# armBandHeaderShield.net
KiCad netlist of a schematic drawn in EAGLE
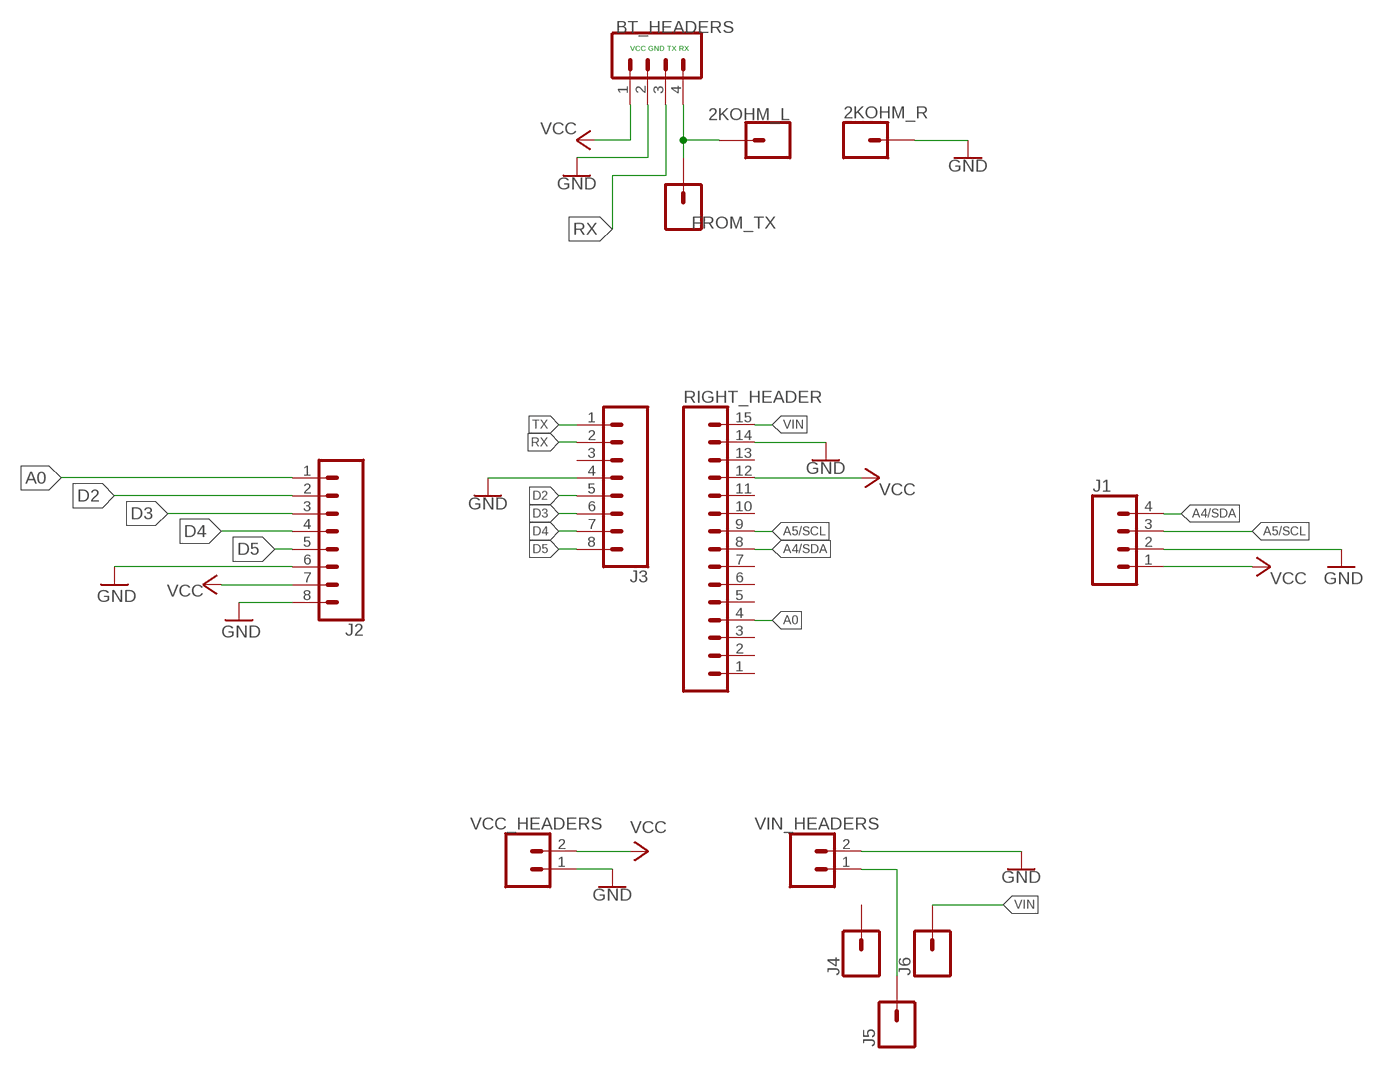
[diagram p0: schematic, sheet 1]

(export (version "E")
  (design (tool "Eeschema 10.0.6"))
  (components
    (comp (ref "2KOHM_L")
      (value "CONN_01")
      (footprint "eagle-import:1X01")
      (libsource (lib "eagle-import") (part "CONN_01"))
    )
    (comp (ref "2KOHM_R")
      (value "CONN_01")
      (footprint "eagle-import:1X01")
      (libsource (lib "eagle-import") (part "CONN_01"))
    )
    (comp (ref "BT_HEADERS")
      (value "CONN_04")
      (footprint "eagle-import:1X04")
      (libsource (lib "eagle-import") (part "CONN_04"))
    )
    (comp (ref "FROM_TX")
      (value "CONN_01")
      (footprint "eagle-import:1X01")
      (libsource (lib "eagle-import") (part "CONN_01"))
    )
    (comp (ref "J1")
      (value "CONN_04")
      (footprint "eagle-import:1X04")
      (libsource (lib "eagle-import") (part "CONN_04"))
    )
    (comp (ref "J2")
      (value "CONN_08\"")
      (footprint "eagle-import:1X08")
      (libsource (lib "eagle-import") (part "CONN_08{dblquote}"))
    )
    (comp (ref "J3")
      (value "CONN_08\"")
      (footprint "eagle-import:1X08")
      (libsource (lib "eagle-import") (part "CONN_08{dblquote}"))
    )
    (comp (ref "J4")
      (value "CONN_01")
      (footprint "eagle-import:1X01")
      (libsource (lib "eagle-import") (part "CONN_01"))
    )
    (comp (ref "J5")
      (value "CONN_01")
      (footprint "eagle-import:1X01")
      (libsource (lib "eagle-import") (part "CONN_01"))
    )
    (comp (ref "J6")
      (value "CONN_01")
      (footprint "eagle-import:1X01")
      (libsource (lib "eagle-import") (part "CONN_01"))
    )
    (comp (ref "RIGHT_HEADER")
      (value "CONN_15")
      (footprint "eagle-import:1X15")
      (libsource (lib "eagle-import") (part "CONN_15"))
    )
    (comp (ref "VCC_HEADERS")
      (value "CONN_02")
      (footprint "eagle-import:1X02")
      (libsource (lib "eagle-import") (part "CONN_02"))
    )
    (comp (ref "VIN_HEADERS")
      (value "CONN_02PTH3")
      (footprint "eagle-import:1X02_LONGPADS")
      (libsource (lib "eagle-import") (part "CONN_02PTH3"))
    )
  )
  (nets
    (net (code "1") (name "A0") (class "Default")
      (node (ref "J2") (pin "1") (pinfunction "1_1") (pintype "passive"))
      (node (ref "RIGHT_HEADER") (pin "4") (pinfunction "4_4") (pintype "passive"))
    )
    (net (code "2") (name "A4{slash}SDA") (class "Default")
      (node (ref "J1") (pin "4") (pinfunction "4_4") (pintype "passive"))
      (node (ref "RIGHT_HEADER") (pin "8") (pinfunction "8_8") (pintype "passive"))
    )
    (net (code "3") (name "A5{slash}SCL") (class "Default")
      (node (ref "J1") (pin "3") (pinfunction "3_3") (pintype "passive"))
      (node (ref "RIGHT_HEADER") (pin "9") (pinfunction "9_9") (pintype "passive"))
    )
    (net (code "4") (name "D2") (class "Default")
      (node (ref "J2") (pin "2") (pinfunction "2_2") (pintype "passive"))
      (node (ref "J3") (pin "5") (pinfunction "5_5") (pintype "passive"))
    )
    (net (code "5") (name "D3") (class "Default")
      (node (ref "J2") (pin "3") (pinfunction "3_3") (pintype "passive"))
      (node (ref "J3") (pin "6") (pinfunction "6_6") (pintype "passive"))
    )
    (net (code "6") (name "D4") (class "Default")
      (node (ref "J2") (pin "4") (pinfunction "4_4") (pintype "passive"))
      (node (ref "J3") (pin "7") (pinfunction "7_7") (pintype "passive"))
    )
    (net (code "7") (name "D5") (class "Default")
      (node (ref "J2") (pin "5") (pinfunction "5_5") (pintype "passive"))
      (node (ref "J3") (pin "8") (pinfunction "8_8") (pintype "passive"))
    )
    (net (code "8") (name "GND") (class "Default")
      (node (ref "2KOHM_R") (pin "1") (pinfunction "1_1") (pintype "passive"))
      (node (ref "BT_HEADERS") (pin "2") (pinfunction "2_2") (pintype "passive"))
      (node (ref "J1") (pin "2") (pinfunction "2_2") (pintype "passive"))
      (node (ref "J2") (pin "6") (pinfunction "6_6") (pintype "passive"))
      (node (ref "J2") (pin "8") (pinfunction "8_8") (pintype "passive"))
      (node (ref "J3") (pin "4") (pinfunction "4_4") (pintype "passive"))
      (node (ref "RIGHT_HEADER") (pin "14") (pinfunction "14_14") (pintype "passive"))
      (node (ref "VCC_HEADERS") (pin "1") (pinfunction "1_1") (pintype "passive"))
      (node (ref "VIN_HEADERS") (pin "2") (pinfunction "2_2") (pintype "passive"))
    )
    (net (code "9") (name "Net-(2KOHM_L-Pad1)") (class "Default")
      (node (ref "2KOHM_L") (pin "1") (pinfunction "1_1") (pintype "passive"))
      (node (ref "BT_HEADERS") (pin "4") (pinfunction "4_4") (pintype "passive"))
      (node (ref "FROM_TX") (pin "1") (pinfunction "1_1") (pintype "passive"))
    )
    (net (code "10") (name "Net-(J5-Pad1)") (class "Default")
      (node (ref "J5") (pin "1") (pinfunction "1_1") (pintype "passive"))
      (node (ref "VIN_HEADERS") (pin "1") (pinfunction "1_1") (pintype "passive"))
    )
    (net (code "11") (name "RX") (class "Default")
      (node (ref "BT_HEADERS") (pin "3") (pinfunction "3_3") (pintype "passive"))
      (node (ref "J3") (pin "2") (pinfunction "2_2") (pintype "passive"))
    )
    (net (code "12") (name "TX") (class "Default")
      (node (ref "J3") (pin "1") (pinfunction "1_1") (pintype "passive"))
    )
    (net (code "13") (name "VCC") (class "Default")
      (node (ref "BT_HEADERS") (pin "1") (pinfunction "1_1") (pintype "passive"))
      (node (ref "J1") (pin "1") (pinfunction "1_1") (pintype "passive"))
      (node (ref "J2") (pin "7") (pinfunction "7_7") (pintype "passive"))
      (node (ref "RIGHT_HEADER") (pin "12") (pinfunction "12_12") (pintype "passive"))
      (node (ref "VCC_HEADERS") (pin "2") (pinfunction "2_2") (pintype "passive"))
    )
    (net (code "14") (name "VIN") (class "Default")
      (node (ref "J6") (pin "1") (pinfunction "1_1") (pintype "passive"))
      (node (ref "RIGHT_HEADER") (pin "15") (pinfunction "15_15") (pintype "passive"))
    )
    (net (code "15") (name "unconnected-(J3-Pad3)") (class "Default")
      (node (ref "J3") (pin "3") (pinfunction "3_3") (pintype "passive"))
    )
    (net (code "16") (name "unconnected-(J4-Pad1)") (class "Default")
      (node (ref "J4") (pin "1") (pinfunction "1_1") (pintype "passive"))
    )
    (net (code "17") (name "unconnected-(RIGHT_HEADER-Pad1)") (class "Default")
      (node (ref "RIGHT_HEADER") (pin "1") (pinfunction "1_1") (pintype "passive"))
    )
    (net (code "18") (name "unconnected-(RIGHT_HEADER-Pad2)") (class "Default")
      (node (ref "RIGHT_HEADER") (pin "2") (pinfunction "2_2") (pintype "passive"))
    )
    (net (code "19") (name "unconnected-(RIGHT_HEADER-Pad3)") (class "Default")
      (node (ref "RIGHT_HEADER") (pin "3") (pinfunction "3_3") (pintype "passive"))
    )
    (net (code "20") (name "unconnected-(RIGHT_HEADER-Pad5)") (class "Default")
      (node (ref "RIGHT_HEADER") (pin "5") (pinfunction "5_5") (pintype "passive"))
    )
    (net (code "21") (name "unconnected-(RIGHT_HEADER-Pad6)") (class "Default")
      (node (ref "RIGHT_HEADER") (pin "6") (pinfunction "6_6") (pintype "passive"))
    )
    (net (code "22") (name "unconnected-(RIGHT_HEADER-Pad7)") (class "Default")
      (node (ref "RIGHT_HEADER") (pin "7") (pinfunction "7_7") (pintype "passive"))
    )
    (net (code "23") (name "unconnected-(RIGHT_HEADER-Pad10)") (class "Default")
      (node (ref "RIGHT_HEADER") (pin "10") (pinfunction "10_10") (pintype "passive"))
    )
    (net (code "24") (name "unconnected-(RIGHT_HEADER-Pad11)") (class "Default")
      (node (ref "RIGHT_HEADER") (pin "11") (pinfunction "11_11") (pintype "passive"))
    )
    (net (code "25") (name "unconnected-(RIGHT_HEADER-Pad13)") (class "Default")
      (node (ref "RIGHT_HEADER") (pin "13") (pinfunction "13_13") (pintype "passive"))
    )
  )
)
